# CAN.net
KiCad netlist of a schematic drawn in Altium Designer
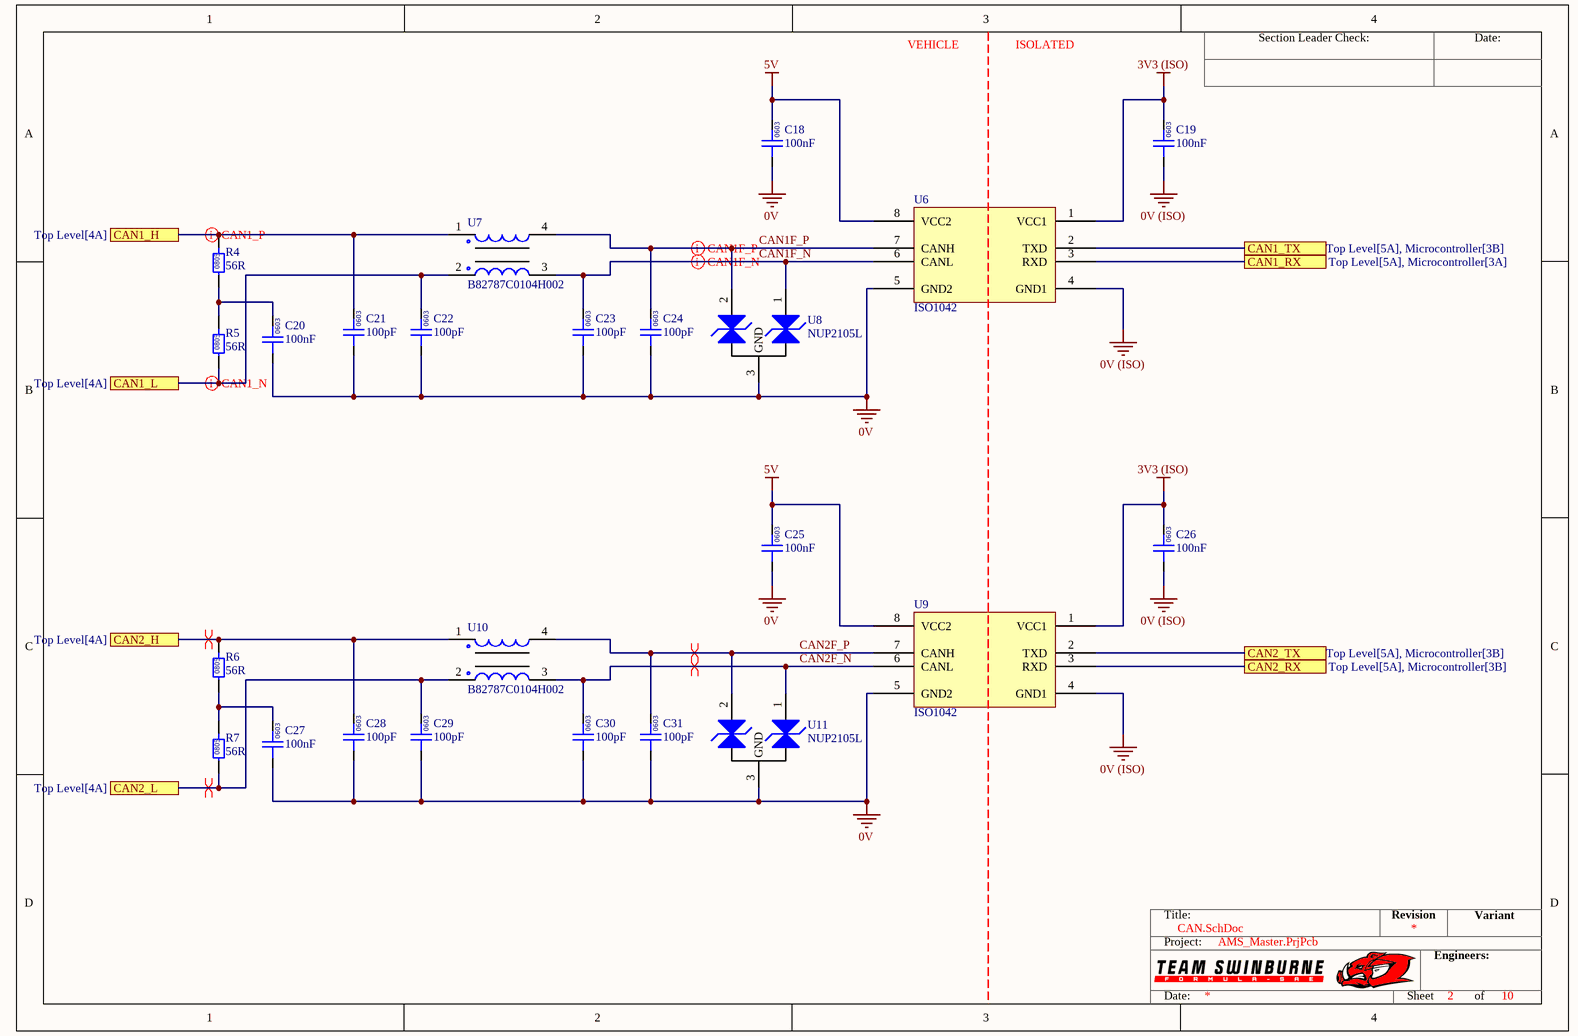
[diagram p0: CAN.SchDoc]

(export (version "E")
  (design (tool "Eeschema 10.0.6"))
  (components
    (comp (ref "C18")
      (value "100nF")
      (footprint "0603")
      (fields
        (field (name "PART NUMBER") "GCM188L81H104KA57D")
        (field (name "MANUFACTURER") "muRata")
        (field (name "TOLERANCE") "±10%")
      )
      (libsource (lib "ts_standard_library") (part "Capacitor 0603"))
    )
    (comp (ref "C19")
      (value "100nF")
      (footprint "0603")
      (fields
        (field (name "PART NUMBER") "GCM188L81H104KA57D")
        (field (name "MANUFACTURER") "muRata")
        (field (name "TOLERANCE") "±10%")
      )
      (libsource (lib "ts_standard_library") (part "Capacitor 0603"))
    )
    (comp (ref "C20")
      (value "100nF")
      (footprint "0603")
      (fields
        (field (name "PART NUMBER") "CL10B104KC8NNNC")
        (field (name "MANUFACTURER") "Samsung Electro-Mechanics")
        (field (name "TOLERANCE") "±10%")
      )
      (libsource (lib "ts_standard_library") (part "Capacitor 0603"))
    )
    (comp (ref "C21")
      (value "100pF")
      (footprint "0603")
      (fields
        (field (name "PART NUMBER") "GRM1885C1H101JA01D")
        (field (name "MANUFACTURER") "Murata Electronics")
        (field (name "TOLERANCE") "±5%")
      )
      (libsource (lib "ts_standard_library") (part "Capacitor 0603"))
    )
    (comp (ref "C22")
      (value "100pF")
      (footprint "0603")
      (fields
        (field (name "PART NUMBER") "GRM1885C1H101JA01D")
        (field (name "MANUFACTURER") "Murata Electronics")
        (field (name "TOLERANCE") "±5%")
      )
      (libsource (lib "ts_standard_library") (part "Capacitor 0603"))
    )
    (comp (ref "C23")
      (value "100pF")
      (footprint "0603")
      (fields
        (field (name "PART NUMBER") "GRM1885C1H101JA01D")
        (field (name "MANUFACTURER") "Murata Electronics")
        (field (name "TOLERANCE") "±5%")
      )
      (libsource (lib "ts_standard_library") (part "Capacitor 0603"))
    )
    (comp (ref "C24")
      (value "100pF")
      (footprint "0603")
      (fields
        (field (name "PART NUMBER") "GRM1885C1H101JA01D")
        (field (name "MANUFACTURER") "Murata Electronics")
        (field (name "TOLERANCE") "±5%")
      )
      (libsource (lib "ts_standard_library") (part "Capacitor 0603"))
    )
    (comp (ref "C25")
      (value "100nF")
      (footprint "0603")
      (fields
        (field (name "PART NUMBER") "GCM188L81H104KA57D")
        (field (name "MANUFACTURER") "muRata")
        (field (name "TOLERANCE") "±10%")
      )
      (libsource (lib "ts_standard_library") (part "Capacitor 0603"))
    )
    (comp (ref "C26")
      (value "100nF")
      (footprint "0603")
      (fields
        (field (name "PART NUMBER") "GCM188L81H104KA57D")
        (field (name "MANUFACTURER") "muRata")
        (field (name "TOLERANCE") "±10%")
      )
      (libsource (lib "ts_standard_library") (part "Capacitor 0603"))
    )
    (comp (ref "C27")
      (value "100nF")
      (footprint "0603")
      (fields
        (field (name "PART NUMBER") "CL10B104KC8NNNC")
        (field (name "MANUFACTURER") "Samsung Electro-Mechanics")
        (field (name "TOLERANCE") "±10%")
      )
      (libsource (lib "ts_standard_library") (part "Capacitor 0603"))
    )
    (comp (ref "C28")
      (value "100pF")
      (footprint "0603")
      (fields
        (field (name "PART NUMBER") "GRM1885C1H101JA01D")
        (field (name "MANUFACTURER") "Murata Electronics")
        (field (name "TOLERANCE") "±5%")
      )
      (libsource (lib "ts_standard_library") (part "Capacitor 0603"))
    )
    (comp (ref "C29")
      (value "100pF")
      (footprint "0603")
      (fields
        (field (name "PART NUMBER") "GRM1885C1H101JA01D")
        (field (name "MANUFACTURER") "Murata Electronics")
        (field (name "TOLERANCE") "±5%")
      )
      (libsource (lib "ts_standard_library") (part "Capacitor 0603"))
    )
    (comp (ref "C30")
      (value "100pF")
      (footprint "0603")
      (fields
        (field (name "PART NUMBER") "GRM1885C1H101JA01D")
        (field (name "MANUFACTURER") "Murata Electronics")
        (field (name "TOLERANCE") "±5%")
      )
      (libsource (lib "ts_standard_library") (part "Capacitor 0603"))
    )
    (comp (ref "C31")
      (value "100pF")
      (footprint "0603")
      (fields
        (field (name "PART NUMBER") "GRM1885C1H101JA01D")
        (field (name "MANUFACTURER") "Murata Electronics")
        (field (name "TOLERANCE") "±5%")
      )
      (libsource (lib "ts_standard_library") (part "Capacitor 0603"))
    )
    (comp (ref "R4")
      (value "56R")
      (footprint "0805")
      (fields
        (field (name "PART NUMBER") "RC0805FR0756RL")
        (field (name "MANUFACTURER") "YAGEO")
        (field (name "TOLERANCE") "0.01")
      )
      (libsource (lib "ts_standard_library") (part "Resistor 0805"))
    )
    (comp (ref "R5")
      (value "56R")
      (footprint "0805")
      (fields
        (field (name "PART NUMBER") "RC0805FR0756RL")
        (field (name "MANUFACTURER") "YAGEO")
        (field (name "TOLERANCE") "0.01")
      )
      (libsource (lib "ts_standard_library") (part "Resistor 0805"))
    )
    (comp (ref "R6")
      (value "56R")
      (footprint "0805")
      (fields
        (field (name "PART NUMBER") "RC0805FR0756RL")
        (field (name "MANUFACTURER") "YAGEO")
        (field (name "TOLERANCE") "0.01")
      )
      (libsource (lib "ts_standard_library") (part "Resistor 0805"))
    )
    (comp (ref "R7")
      (value "56R")
      (footprint "0805")
      (fields
        (field (name "PART NUMBER") "RC0805FR0756RL")
        (field (name "MANUFACTURER") "YAGEO")
        (field (name "TOLERANCE") "0.01")
      )
      (libsource (lib "ts_standard_library") (part "Resistor 0805"))
    )
    (comp (ref "U6")
      (value "ISO1042")
      (footprint "TI-SOIC-8")
      (description "IC CAN TRANSCEIVER 1/1 8SOIC")
      (fields
        (field (name "MANUFACTURER") "Texas Instruments")
        (field (name "DIGIKEY PART NUMBER") "296-ISO1042BQDWVQ1-ND")
      )
      (libsource (lib "ts_standard_library") (part "ISO1042"))
    )
    (comp (ref "U7")
      (value "B82787C0104H002")
      (footprint "TDK 4-PC Pad")
      (fields
        (field (name "MANUFACTURER") "EPCOS (TDK)")
        (field (name "DIGIKEY PART NUMBER") "495-4598-1-ND")
      )
      (libsource (lib "ts_standard_library") (part "B82787C0104H002"))
    )
    (comp (ref "U8")
      (value "NUP2105L")
      (footprint "ON SOT-23")
      (description "Dual Line CAN Bus Protector")
      (fields
        (field (name "MANUFACTURER") "ON Semiconductor")
        (field (name "DIGIKEY PART NUMBER") "NUP2105LT1GOSCT-ND")
      )
      (libsource (lib "ts_standard_library") (part "NUP2105L"))
    )
    (comp (ref "U9")
      (value "ISO1042")
      (footprint "TI-SOIC-8")
      (description "IC CAN TRANSCEIVER 1/1 8SOIC")
      (fields
        (field (name "MANUFACTURER") "Texas Instruments")
        (field (name "DIGIKEY PART NUMBER") "296-ISO1042BQDWVQ1-ND")
      )
      (libsource (lib "ts_standard_library") (part "ISO1042"))
    )
    (comp (ref "U10")
      (value "B82787C0104H002")
      (footprint "TDK 4-PC Pad")
      (fields
        (field (name "MANUFACTURER") "EPCOS (TDK)")
        (field (name "DIGIKEY PART NUMBER") "495-4598-1-ND")
      )
      (libsource (lib "ts_standard_library") (part "B82787C0104H002"))
    )
    (comp (ref "U11")
      (value "NUP2105L")
      (footprint "ON SOT-23")
      (description "Dual Line CAN Bus Protector")
      (fields
        (field (name "MANUFACTURER") "ON Semiconductor")
        (field (name "DIGIKEY PART NUMBER") "NUP2105LT1GOSCT-ND")
      )
      (libsource (lib "ts_standard_library") (part "NUP2105L"))
    )
  )
  (nets
    (net (code "1") (name "/CAN1F_N") (class "Default")
      (node (ref "C23") (pin "2") (pinfunction "2_2") (pintype "passive"))
      (node (ref "U6") (pin "6") (pinfunction "CANL_6") (pintype "passive"))
      (node (ref "U7") (pin "3") (pinfunction "3_3") (pintype "passive"))
      (node (ref "U8") (pin "1") (pinfunction "CAN_H_1") (pintype "passive"))
    )
    (net (code "2") (name "/CAN1F_P") (class "Default")
      (node (ref "C24") (pin "2") (pinfunction "2_2") (pintype "passive"))
      (node (ref "U6") (pin "7") (pinfunction "CANH_7") (pintype "passive"))
      (node (ref "U7") (pin "4") (pinfunction "4_4") (pintype "passive"))
      (node (ref "U8") (pin "2") (pinfunction "CAN_L_2") (pintype "passive"))
    )
    (net (code "3") (name "/CAN1_H") (class "Default")
      (node (ref "C21") (pin "2") (pinfunction "2_2") (pintype "passive"))
      (node (ref "R4") (pin "2") (pinfunction "2_2") (pintype "passive"))
      (node (ref "U7") (pin "1") (pinfunction "1_1") (pintype "passive"))
    )
    (net (code "4") (name "/CAN1_L") (class "Default")
      (node (ref "C22") (pin "2") (pinfunction "2_2") (pintype "passive"))
      (node (ref "R5") (pin "1") (pinfunction "1_1") (pintype "passive"))
      (node (ref "U7") (pin "2") (pinfunction "2_2") (pintype "passive"))
    )
    (net (code "5") (name "/CAN1_RX") (class "Default")
      (node (ref "U6") (pin "3") (pinfunction "RXD_3") (pintype "passive"))
    )
    (net (code "6") (name "/CAN1_TX") (class "Default")
      (node (ref "U6") (pin "2") (pinfunction "TXD_2") (pintype "passive"))
    )
    (net (code "7") (name "/CAN2F_N") (class "Default")
      (node (ref "C30") (pin "2") (pinfunction "2_2") (pintype "passive"))
      (node (ref "U10") (pin "3") (pinfunction "3_3") (pintype "passive"))
      (node (ref "U11") (pin "1") (pinfunction "CAN_H_1") (pintype "passive"))
      (node (ref "U9") (pin "6") (pinfunction "CANL_6") (pintype "passive"))
    )
    (net (code "8") (name "/CAN2F_P") (class "Default")
      (node (ref "C31") (pin "2") (pinfunction "2_2") (pintype "passive"))
      (node (ref "U10") (pin "4") (pinfunction "4_4") (pintype "passive"))
      (node (ref "U11") (pin "2") (pinfunction "CAN_L_2") (pintype "passive"))
      (node (ref "U9") (pin "7") (pinfunction "CANH_7") (pintype "passive"))
    )
    (net (code "9") (name "/CAN2_H") (class "Default")
      (node (ref "C28") (pin "2") (pinfunction "2_2") (pintype "passive"))
      (node (ref "R6") (pin "2") (pinfunction "2_2") (pintype "passive"))
      (node (ref "U10") (pin "1") (pinfunction "1_1") (pintype "passive"))
    )
    (net (code "10") (name "/CAN2_L") (class "Default")
      (node (ref "C29") (pin "2") (pinfunction "2_2") (pintype "passive"))
      (node (ref "R7") (pin "1") (pinfunction "1_1") (pintype "passive"))
      (node (ref "U10") (pin "2") (pinfunction "2_2") (pintype "passive"))
    )
    (net (code "11") (name "/CAN2_RX") (class "Default")
      (node (ref "U9") (pin "3") (pinfunction "RXD_3") (pintype "passive"))
    )
    (net (code "12") (name "/CAN2_TX") (class "Default")
      (node (ref "U9") (pin "2") (pinfunction "TXD_2") (pintype "passive"))
    )
    (net (code "13") (name "0V") (class "Default")
      (node (ref "C18") (pin "1") (pinfunction "1_1") (pintype "passive"))
      (node (ref "C20") (pin "1") (pinfunction "1_1") (pintype "passive"))
      (node (ref "C21") (pin "1") (pinfunction "1_1") (pintype "passive"))
      (node (ref "C22") (pin "1") (pinfunction "1_1") (pintype "passive"))
      (node (ref "C23") (pin "1") (pinfunction "1_1") (pintype "passive"))
      (node (ref "C24") (pin "1") (pinfunction "1_1") (pintype "passive"))
      (node (ref "C25") (pin "1") (pinfunction "1_1") (pintype "passive"))
      (node (ref "C27") (pin "1") (pinfunction "1_1") (pintype "passive"))
      (node (ref "C28") (pin "1") (pinfunction "1_1") (pintype "passive"))
      (node (ref "C29") (pin "1") (pinfunction "1_1") (pintype "passive"))
      (node (ref "C30") (pin "1") (pinfunction "1_1") (pintype "passive"))
      (node (ref "C31") (pin "1") (pinfunction "1_1") (pintype "passive"))
      (node (ref "U11") (pin "3") (pinfunction "GND_3") (pintype "passive"))
      (node (ref "U6") (pin "5") (pinfunction "GND2_5") (pintype "passive"))
      (node (ref "U8") (pin "3") (pinfunction "GND_3") (pintype "passive"))
      (node (ref "U9") (pin "5") (pinfunction "GND2_5") (pintype "passive"))
    )
    (net (code "14") (name "0V (ISO)") (class "Default")
      (node (ref "C19") (pin "1") (pinfunction "1_1") (pintype "passive"))
      (node (ref "C26") (pin "1") (pinfunction "1_1") (pintype "passive"))
      (node (ref "U6") (pin "4") (pinfunction "GND1_4") (pintype "passive"))
      (node (ref "U9") (pin "4") (pinfunction "GND1_4") (pintype "passive"))
    )
    (net (code "15") (name "3V3 (ISO)") (class "Default")
      (node (ref "C19") (pin "2") (pinfunction "2_2") (pintype "passive"))
      (node (ref "C26") (pin "2") (pinfunction "2_2") (pintype "passive"))
      (node (ref "U6") (pin "1") (pinfunction "VCC1_1") (pintype "passive"))
      (node (ref "U9") (pin "1") (pinfunction "VCC1_1") (pintype "passive"))
    )
    (net (code "16") (name "5V") (class "Default")
      (node (ref "C18") (pin "2") (pinfunction "2_2") (pintype "passive"))
      (node (ref "C25") (pin "2") (pinfunction "2_2") (pintype "passive"))
      (node (ref "U6") (pin "8") (pinfunction "VCC2_8") (pintype "passive"))
      (node (ref "U9") (pin "8") (pinfunction "VCC2_8") (pintype "passive"))
    )
    (net (code "17") (name "Net-(C20-Pad2)") (class "Default")
      (node (ref "C20") (pin "2") (pinfunction "2_2") (pintype "passive"))
      (node (ref "R4") (pin "1") (pinfunction "1_1") (pintype "passive"))
      (node (ref "R5") (pin "2") (pinfunction "2_2") (pintype "passive"))
    )
    (net (code "18") (name "Net-(C27-Pad2)") (class "Default")
      (node (ref "C27") (pin "2") (pinfunction "2_2") (pintype "passive"))
      (node (ref "R6") (pin "1") (pinfunction "1_1") (pintype "passive"))
      (node (ref "R7") (pin "2") (pinfunction "2_2") (pintype "passive"))
    )
  )
)
